# bldc_driver.net
KiCad netlist of a schematic drawn in EAGLE
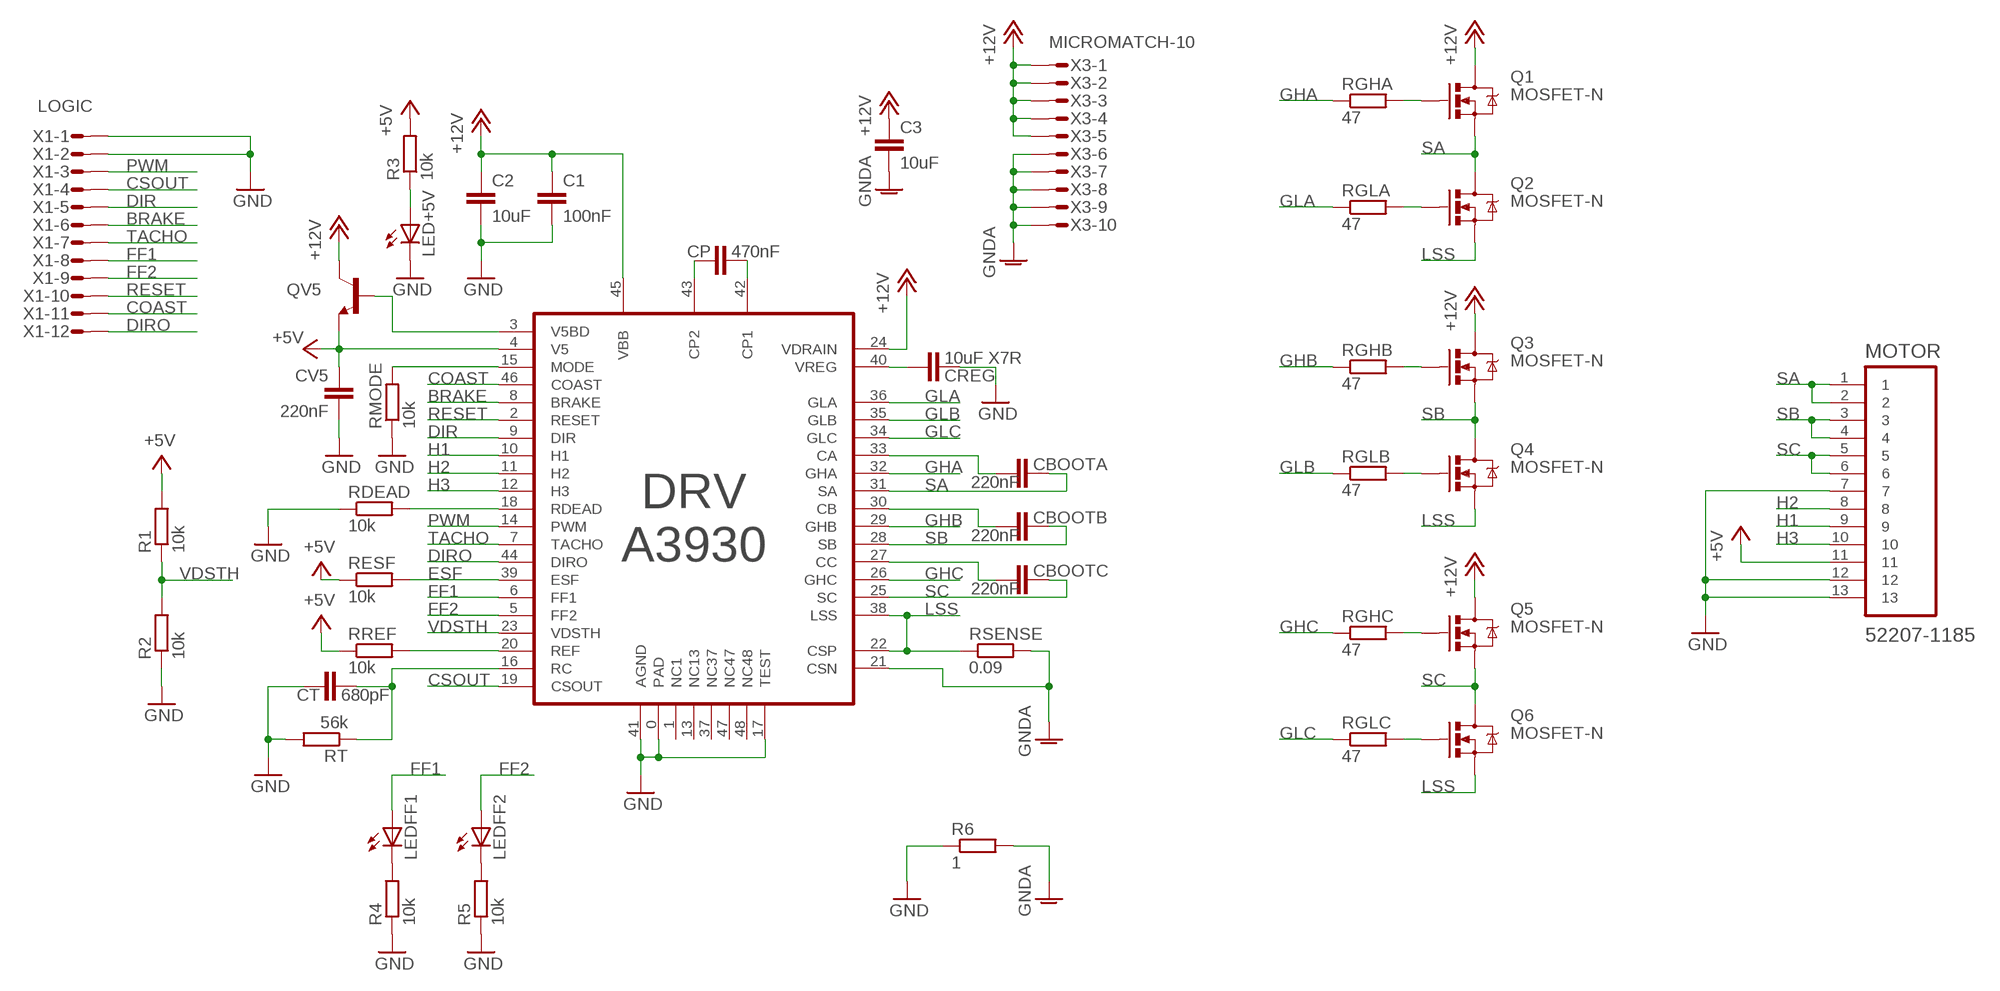
[diagram p0: schematic, sheet 1]

(export (version "E")
  (design (tool "Eeschema 10.0.6"))
  (components
    (comp (ref "C1")
      (value "100nF")
      (footprint "eagle-import:C0603")
      (libsource (lib "eagle-import") (part "C-EUC0603"))
    )
    (comp (ref "C2")
      (value "10uF")
      (footprint "eagle-import:C1206K")
      (libsource (lib "eagle-import") (part "C-EUC1206K"))
    )
    (comp (ref "C3")
      (value "10uF")
      (footprint "eagle-import:C1206K")
      (libsource (lib "eagle-import") (part "C-EUC1206K"))
    )
    (comp (ref "CBOOTA")
      (value "220nF")
      (footprint "eagle-import:C0603")
      (libsource (lib "eagle-import") (part "C-EUC0603"))
    )
    (comp (ref "CBOOTB")
      (value "220nF")
      (footprint "eagle-import:C0603")
      (libsource (lib "eagle-import") (part "C-EUC0603"))
    )
    (comp (ref "CBOOTC")
      (value "220nF")
      (footprint "eagle-import:C0603")
      (libsource (lib "eagle-import") (part "C-EUC0603"))
    )
    (comp (ref "CP")
      (value "470nF")
      (footprint "eagle-import:C0603")
      (libsource (lib "eagle-import") (part "C-EUC0603"))
    )
    (comp (ref "CREG")
      (value "10uF X7R")
      (footprint "eagle-import:C1206K")
      (libsource (lib "eagle-import") (part "C-EUC1206K"))
    )
    (comp (ref "CT")
      (value "680pF")
      (footprint "eagle-import:C0603")
      (libsource (lib "eagle-import") (part "C-EUC0603"))
    )
    (comp (ref "CV5")
      (value "220nF")
      (footprint "eagle-import:C0603")
      (libsource (lib "eagle-import") (part "C-EUC0603"))
    )
    (comp (ref "DRV")
      (value "A3930")
      (footprint "eagle-import:LQFP-48")
      (libsource (lib "eagle-import") (part "A3930"))
    )
    (comp (ref "LED+5V")
      (value "LEDCHIPLED_0603")
      (footprint "eagle-import:CHIPLED_0603")
      (libsource (lib "eagle-import") (part "LEDCHIPLED_0603"))
    )
    (comp (ref "LEDFF1")
      (value "LEDCHIPLED_0603")
      (footprint "eagle-import:CHIPLED_0603")
      (libsource (lib "eagle-import") (part "LEDCHIPLED_0603"))
    )
    (comp (ref "LEDFF2")
      (value "LEDCHIPLED_0603")
      (footprint "eagle-import:CHIPLED_0603")
      (libsource (lib "eagle-import") (part "LEDCHIPLED_0603"))
    )
    (comp (ref "MOTOR")
      (value "52207-1185")
      (footprint "eagle-import:MOLEX_52207-1185")
      (fields (field (name "MPN") "52207-1085"))
      (libsource (lib "eagle-import") (part "52207-1185"))
    )
    (comp (ref "Q1")
      (value "MOSFET-N")
      (footprint "eagle-import:SO08")
      (libsource (lib "eagle-import") (part "MOSFET-NCHANNELFDS6630A"))
    )
    (comp (ref "Q2")
      (value "MOSFET-N")
      (footprint "eagle-import:SO08")
      (libsource (lib "eagle-import") (part "MOSFET-NCHANNELFDS6630A"))
    )
    (comp (ref "Q3")
      (value "MOSFET-N")
      (footprint "eagle-import:SO08")
      (libsource (lib "eagle-import") (part "MOSFET-NCHANNELFDS6630A"))
    )
    (comp (ref "Q4")
      (value "MOSFET-N")
      (footprint "eagle-import:SO08")
      (libsource (lib "eagle-import") (part "MOSFET-NCHANNELFDS6630A"))
    )
    (comp (ref "Q5")
      (value "MOSFET-N")
      (footprint "eagle-import:SO08")
      (libsource (lib "eagle-import") (part "MOSFET-NCHANNELFDS6630A"))
    )
    (comp (ref "Q6")
      (value "MOSFET-N")
      (footprint "eagle-import:SO08")
      (libsource (lib "eagle-import") (part "MOSFET-NCHANNELFDS6630A"))
    )
    (comp (ref "QV5")
      (value "TRANSISTOR_NPNSOT23")
      (footprint "eagle-import:SOT23")
      (libsource (lib "eagle-import") (part "TRANSISTOR_NPNSOT23"))
    )
    (comp (ref "R1")
      (value "10k")
      (footprint "eagle-import:R0603")
      (libsource (lib "eagle-import") (part "R-EU_R0603"))
    )
    (comp (ref "R2")
      (value "10k")
      (footprint "eagle-import:R0603")
      (libsource (lib "eagle-import") (part "R-EU_R0603"))
    )
    (comp (ref "R3")
      (value "10k")
      (footprint "eagle-import:R0603")
      (libsource (lib "eagle-import") (part "R-EU_R0603"))
    )
    (comp (ref "R4")
      (value "10k")
      (footprint "eagle-import:R0603")
      (libsource (lib "eagle-import") (part "R-EU_R0603"))
    )
    (comp (ref "R5")
      (value "10k")
      (footprint "eagle-import:R0603")
      (libsource (lib "eagle-import") (part "R-EU_R0603"))
    )
    (comp (ref "R6")
      (value "1")
      (footprint "eagle-import:R0603")
      (libsource (lib "eagle-import") (part "R-EU_R0603"))
    )
    (comp (ref "RDEAD")
      (value "10k")
      (footprint "eagle-import:R0603")
      (libsource (lib "eagle-import") (part "R-EU_R0603"))
    )
    (comp (ref "RESF")
      (value "10k")
      (footprint "eagle-import:R0603")
      (libsource (lib "eagle-import") (part "R-EU_R0603"))
    )
    (comp (ref "RGHA")
      (value "47")
      (footprint "eagle-import:R0603")
      (libsource (lib "eagle-import") (part "R-EU_R0603"))
    )
    (comp (ref "RGHB")
      (value "47")
      (footprint "eagle-import:R0603")
      (libsource (lib "eagle-import") (part "R-EU_R0603"))
    )
    (comp (ref "RGHC")
      (value "47")
      (footprint "eagle-import:R0603")
      (libsource (lib "eagle-import") (part "R-EU_R0603"))
    )
    (comp (ref "RGLA")
      (value "47")
      (footprint "eagle-import:R0603")
      (libsource (lib "eagle-import") (part "R-EU_R0603"))
    )
    (comp (ref "RGLB")
      (value "47")
      (footprint "eagle-import:R0603")
      (libsource (lib "eagle-import") (part "R-EU_R0603"))
    )
    (comp (ref "RGLC")
      (value "47")
      (footprint "eagle-import:R0603")
      (libsource (lib "eagle-import") (part "R-EU_R0603"))
    )
    (comp (ref "RMODE")
      (value "10k")
      (footprint "eagle-import:R0603")
      (libsource (lib "eagle-import") (part "R-EU_R0603"))
    )
    (comp (ref "RREF")
      (value "10k")
      (footprint "eagle-import:R0603")
      (libsource (lib "eagle-import") (part "R-EU_R0603"))
    )
    (comp (ref "RSENSE")
      (value "0.09")
      (footprint "eagle-import:R2010")
      (libsource (lib "eagle-import") (part "R-EU_R2010"))
    )
    (comp (ref "RT")
      (value "56k")
      (footprint "eagle-import:R0603")
      (libsource (lib "eagle-import") (part "R-EU_R0603"))
    )
    (comp (ref "X1")
      (value "LOGIC")
      (footprint "eagle-import:MICROMATCH-12")
      (fields (field (name "MF") "FARNELL") (field (name "MPN") "8-215464-2"))
      (libsource (lib "eagle-import") (part "MICROMATCH-12"))
    )
    (comp (ref "X3")
      (value "MICROMATCH-10")
      (footprint "eagle-import:MICROMATCH-10")
      (fields (field (name "MF") "FARNELL") (field (name "MPN") "8-215464-0"))
      (libsource (lib "eagle-import") (part "MICROMATCH-10"))
    )
  )
  (nets
    (net (code "1") (name "+5V") (class "Default")
      (node (ref "CV5") (pin "2") (pinfunction "2_2") (pintype "passive"))
      (node (ref "DRV") (pin "4") (pinfunction "V5_4") (pintype "bidirectional"))
      (node (ref "MOTOR") (pin "11") (pinfunction "11_11") (pintype "passive"))
      (node (ref "QV5") (pin "2") (pinfunction "E_2") (pintype "passive"))
      (node (ref "R1") (pin "2") (pinfunction "2_2") (pintype "passive"))
      (node (ref "R3") (pin "2") (pinfunction "2_2") (pintype "passive"))
      (node (ref "RESF") (pin "1") (pinfunction "1_1") (pintype "passive"))
      (node (ref "RREF") (pin "1") (pinfunction "1_1") (pintype "passive"))
    )
    (net (code "2") (name "+12V") (class "Default")
      (node (ref "C1") (pin "1") (pinfunction "1_1") (pintype "passive"))
      (node (ref "C2") (pin "1") (pinfunction "1_1") (pintype "passive"))
      (node (ref "C3") (pin "1") (pinfunction "1_1") (pintype "passive"))
      (node (ref "DRV") (pin "24") (pinfunction "VDRAIN_24") (pintype "bidirectional"))
      (node (ref "DRV") (pin "45") (pinfunction "VBB_45") (pintype "bidirectional"))
      (node (ref "Q1") (pin "5") (pinfunction "D_5") (pintype "passive"))
      (node (ref "Q1") (pin "6") (pinfunction "D_6") (pintype "passive"))
      (node (ref "Q1") (pin "7") (pinfunction "D_7") (pintype "passive"))
      (node (ref "Q1") (pin "8") (pinfunction "D_8") (pintype "passive"))
      (node (ref "Q3") (pin "5") (pinfunction "D_5") (pintype "passive"))
      (node (ref "Q3") (pin "6") (pinfunction "D_6") (pintype "passive"))
      (node (ref "Q3") (pin "7") (pinfunction "D_7") (pintype "passive"))
      (node (ref "Q3") (pin "8") (pinfunction "D_8") (pintype "passive"))
      (node (ref "Q5") (pin "5") (pinfunction "D_5") (pintype "passive"))
      (node (ref "Q5") (pin "6") (pinfunction "D_6") (pintype "passive"))
      (node (ref "Q5") (pin "7") (pinfunction "D_7") (pintype "passive"))
      (node (ref "Q5") (pin "8") (pinfunction "D_8") (pintype "passive"))
      (node (ref "QV5") (pin "3") (pinfunction "C_3") (pintype "passive"))
      (node (ref "X3") (pin "1") (pinfunction "S_1") (pintype "passive"))
      (node (ref "X3") (pin "2") (pinfunction "S_2") (pintype "passive"))
      (node (ref "X3") (pin "3") (pinfunction "S_3") (pintype "passive"))
      (node (ref "X3") (pin "4") (pinfunction "S_4") (pintype "passive"))
      (node (ref "X3") (pin "5") (pinfunction "S_5") (pintype "passive"))
    )
    (net (code "3") (name "/BRAKE") (class "Default")
      (node (ref "DRV") (pin "8") (pinfunction "BRAKE_8") (pintype "bidirectional"))
      (node (ref "X1") (pin "6") (pinfunction "S_6") (pintype "passive"))
    )
    (net (code "4") (name "/COAST") (class "Default")
      (node (ref "DRV") (pin "46") (pinfunction "COAST_46") (pintype "bidirectional"))
      (node (ref "X1") (pin "11") (pinfunction "S_11") (pintype "passive"))
    )
    (net (code "5") (name "/CSOUT") (class "Default")
      (node (ref "DRV") (pin "19") (pinfunction "CSOUT_19") (pintype "bidirectional"))
      (node (ref "X1") (pin "4") (pinfunction "S_4") (pintype "passive"))
    )
    (net (code "6") (name "/DIR") (class "Default")
      (node (ref "DRV") (pin "9") (pinfunction "DIR_9") (pintype "bidirectional"))
      (node (ref "X1") (pin "5") (pinfunction "S_5") (pintype "passive"))
    )
    (net (code "7") (name "/DIRO") (class "Default")
      (node (ref "DRV") (pin "44") (pinfunction "DIRO_44") (pintype "bidirectional"))
      (node (ref "X1") (pin "12") (pinfunction "S_12") (pintype "passive"))
    )
    (net (code "8") (name "/ESF") (class "Default")
      (node (ref "DRV") (pin "39") (pinfunction "ESF_39") (pintype "bidirectional"))
      (node (ref "RESF") (pin "2") (pinfunction "2_2") (pintype "passive"))
    )
    (net (code "9") (name "/FF1") (class "Default")
      (node (ref "DRV") (pin "6") (pinfunction "FF1_6") (pintype "bidirectional"))
      (node (ref "LEDFF1") (pin "A") (pinfunction "A_A") (pintype "passive"))
      (node (ref "X1") (pin "8") (pinfunction "S_8") (pintype "passive"))
    )
    (net (code "10") (name "/FF2") (class "Default")
      (node (ref "DRV") (pin "5") (pinfunction "FF2_5") (pintype "bidirectional"))
      (node (ref "LEDFF2") (pin "A") (pinfunction "A_A") (pintype "passive"))
      (node (ref "X1") (pin "9") (pinfunction "S_9") (pintype "passive"))
    )
    (net (code "11") (name "/GHA") (class "Default")
      (node (ref "DRV") (pin "32") (pinfunction "GHA_32") (pintype "bidirectional"))
      (node (ref "RGHA") (pin "1") (pinfunction "1_1") (pintype "passive"))
    )
    (net (code "12") (name "/GHB") (class "Default")
      (node (ref "DRV") (pin "29") (pinfunction "GHB_29") (pintype "bidirectional"))
      (node (ref "RGHB") (pin "1") (pinfunction "1_1") (pintype "passive"))
    )
    (net (code "13") (name "/GHC") (class "Default")
      (node (ref "DRV") (pin "26") (pinfunction "GHC_26") (pintype "bidirectional"))
      (node (ref "RGHC") (pin "1") (pinfunction "1_1") (pintype "passive"))
    )
    (net (code "14") (name "/GLA") (class "Default")
      (node (ref "DRV") (pin "36") (pinfunction "GLA_36") (pintype "bidirectional"))
      (node (ref "RGLA") (pin "1") (pinfunction "1_1") (pintype "passive"))
    )
    (net (code "15") (name "/GLB") (class "Default")
      (node (ref "DRV") (pin "35") (pinfunction "GLB_35") (pintype "bidirectional"))
      (node (ref "RGLB") (pin "1") (pinfunction "1_1") (pintype "passive"))
    )
    (net (code "16") (name "/GLC") (class "Default")
      (node (ref "DRV") (pin "34") (pinfunction "GLC_34") (pintype "bidirectional"))
      (node (ref "RGLC") (pin "1") (pinfunction "1_1") (pintype "passive"))
    )
    (net (code "17") (name "/H1") (class "Default")
      (node (ref "DRV") (pin "10") (pinfunction "H1_10") (pintype "bidirectional"))
      (node (ref "MOTOR") (pin "9") (pinfunction "9_9") (pintype "passive"))
    )
    (net (code "18") (name "/H2") (class "Default")
      (node (ref "DRV") (pin "11") (pinfunction "H2_11") (pintype "bidirectional"))
      (node (ref "MOTOR") (pin "8") (pinfunction "8_8") (pintype "passive"))
    )
    (net (code "19") (name "/H3") (class "Default")
      (node (ref "DRV") (pin "12") (pinfunction "H3_12") (pintype "bidirectional"))
      (node (ref "MOTOR") (pin "10") (pinfunction "10_10") (pintype "passive"))
    )
    (net (code "20") (name "/LSS") (class "Default")
      (node (ref "DRV") (pin "22") (pinfunction "CSP_22") (pintype "bidirectional"))
      (node (ref "DRV") (pin "38") (pinfunction "LSS_38") (pintype "bidirectional"))
      (node (ref "Q2") (pin "1") (pinfunction "S_1") (pintype "passive"))
      (node (ref "Q2") (pin "2") (pinfunction "S_2") (pintype "passive"))
      (node (ref "Q2") (pin "3") (pinfunction "S_3") (pintype "passive"))
      (node (ref "Q4") (pin "1") (pinfunction "S_1") (pintype "passive"))
      (node (ref "Q4") (pin "2") (pinfunction "S_2") (pintype "passive"))
      (node (ref "Q4") (pin "3") (pinfunction "S_3") (pintype "passive"))
      (node (ref "Q6") (pin "1") (pinfunction "S_1") (pintype "passive"))
      (node (ref "Q6") (pin "2") (pinfunction "S_2") (pintype "passive"))
      (node (ref "Q6") (pin "3") (pinfunction "S_3") (pintype "passive"))
      (node (ref "RSENSE") (pin "1") (pinfunction "1_1") (pintype "passive"))
    )
    (net (code "21") (name "/PWM") (class "Default")
      (node (ref "DRV") (pin "14") (pinfunction "PWM_14") (pintype "bidirectional"))
      (node (ref "X1") (pin "3") (pinfunction "S_3") (pintype "passive"))
    )
    (net (code "22") (name "/RESET") (class "Default")
      (node (ref "DRV") (pin "2") (pinfunction "RESET_2") (pintype "bidirectional"))
      (node (ref "X1") (pin "10") (pinfunction "S_10") (pintype "passive"))
    )
    (net (code "23") (name "/SA") (class "Default")
      (node (ref "CBOOTA") (pin "2") (pinfunction "2_2") (pintype "passive"))
      (node (ref "DRV") (pin "31") (pinfunction "SA_31") (pintype "bidirectional"))
      (node (ref "MOTOR") (pin "1") (pinfunction "1_1") (pintype "passive"))
      (node (ref "MOTOR") (pin "2") (pinfunction "2_2") (pintype "passive"))
      (node (ref "Q1") (pin "1") (pinfunction "S_1") (pintype "passive"))
      (node (ref "Q1") (pin "2") (pinfunction "S_2") (pintype "passive"))
      (node (ref "Q1") (pin "3") (pinfunction "S_3") (pintype "passive"))
      (node (ref "Q2") (pin "5") (pinfunction "D_5") (pintype "passive"))
      (node (ref "Q2") (pin "6") (pinfunction "D_6") (pintype "passive"))
      (node (ref "Q2") (pin "7") (pinfunction "D_7") (pintype "passive"))
      (node (ref "Q2") (pin "8") (pinfunction "D_8") (pintype "passive"))
    )
    (net (code "24") (name "/SB") (class "Default")
      (node (ref "CBOOTB") (pin "2") (pinfunction "2_2") (pintype "passive"))
      (node (ref "DRV") (pin "28") (pinfunction "SB_28") (pintype "bidirectional"))
      (node (ref "MOTOR") (pin "3") (pinfunction "3_3") (pintype "passive"))
      (node (ref "MOTOR") (pin "4") (pinfunction "4_4") (pintype "passive"))
      (node (ref "Q3") (pin "1") (pinfunction "S_1") (pintype "passive"))
      (node (ref "Q3") (pin "2") (pinfunction "S_2") (pintype "passive"))
      (node (ref "Q3") (pin "3") (pinfunction "S_3") (pintype "passive"))
      (node (ref "Q4") (pin "5") (pinfunction "D_5") (pintype "passive"))
      (node (ref "Q4") (pin "6") (pinfunction "D_6") (pintype "passive"))
      (node (ref "Q4") (pin "7") (pinfunction "D_7") (pintype "passive"))
      (node (ref "Q4") (pin "8") (pinfunction "D_8") (pintype "passive"))
    )
    (net (code "25") (name "/SC") (class "Default")
      (node (ref "CBOOTC") (pin "2") (pinfunction "2_2") (pintype "passive"))
      (node (ref "DRV") (pin "25") (pinfunction "SC_25") (pintype "bidirectional"))
      (node (ref "MOTOR") (pin "5") (pinfunction "5_5") (pintype "passive"))
      (node (ref "MOTOR") (pin "6") (pinfunction "6_6") (pintype "passive"))
      (node (ref "Q5") (pin "1") (pinfunction "S_1") (pintype "passive"))
      (node (ref "Q5") (pin "2") (pinfunction "S_2") (pintype "passive"))
      (node (ref "Q5") (pin "3") (pinfunction "S_3") (pintype "passive"))
      (node (ref "Q6") (pin "5") (pinfunction "D_5") (pintype "passive"))
      (node (ref "Q6") (pin "6") (pinfunction "D_6") (pintype "passive"))
      (node (ref "Q6") (pin "7") (pinfunction "D_7") (pintype "passive"))
      (node (ref "Q6") (pin "8") (pinfunction "D_8") (pintype "passive"))
    )
    (net (code "26") (name "/TACHO") (class "Default")
      (node (ref "DRV") (pin "7") (pinfunction "TACHO_7") (pintype "bidirectional"))
      (node (ref "X1") (pin "7") (pinfunction "S_7") (pintype "passive"))
    )
    (net (code "27") (name "/VDSTH") (class "Default")
      (node (ref "DRV") (pin "23") (pinfunction "VDSTH_23") (pintype "bidirectional"))
      (node (ref "R1") (pin "1") (pinfunction "1_1") (pintype "passive"))
      (node (ref "R2") (pin "2") (pinfunction "2_2") (pintype "passive"))
    )
    (net (code "28") (name "GND") (class "Default")
      (node (ref "C1") (pin "2") (pinfunction "2_2") (pintype "passive"))
      (node (ref "C2") (pin "2") (pinfunction "2_2") (pintype "passive"))
      (node (ref "CREG") (pin "2") (pinfunction "2_2") (pintype "passive"))
      (node (ref "CT") (pin "2") (pinfunction "2_2") (pintype "passive"))
      (node (ref "CV5") (pin "1") (pinfunction "1_1") (pintype "passive"))
      (node (ref "DRV") (pin "0") (pinfunction "PAD_0") (pintype "bidirectional"))
      (node (ref "DRV") (pin "17") (pinfunction "TEST_17") (pintype "bidirectional"))
      (node (ref "DRV") (pin "41") (pinfunction "AGND_41") (pintype "bidirectional"))
      (node (ref "LED+5V") (pin "C") (pinfunction "C_C") (pintype "passive"))
      (node (ref "MOTOR") (pin "12") (pinfunction "12_12") (pintype "passive"))
      (node (ref "MOTOR") (pin "13") (pinfunction "13_13") (pintype "passive"))
      (node (ref "MOTOR") (pin "7") (pinfunction "7_7") (pintype "passive"))
      (node (ref "R2") (pin "1") (pinfunction "1_1") (pintype "passive"))
      (node (ref "R4") (pin "1") (pinfunction "1_1") (pintype "passive"))
      (node (ref "R5") (pin "1") (pinfunction "1_1") (pintype "passive"))
      (node (ref "R6") (pin "1") (pinfunction "1_1") (pintype "passive"))
      (node (ref "RDEAD") (pin "1") (pinfunction "1_1") (pintype "passive"))
      (node (ref "RMODE") (pin "1") (pinfunction "1_1") (pintype "passive"))
      (node (ref "RT") (pin "2") (pinfunction "2_2") (pintype "passive"))
      (node (ref "X1") (pin "1") (pinfunction "S_1") (pintype "passive"))
      (node (ref "X1") (pin "2") (pinfunction "S_2") (pintype "passive"))
    )
    (net (code "29") (name "GNDA") (class "Default")
      (node (ref "C3") (pin "2") (pinfunction "2_2") (pintype "passive"))
      (node (ref "DRV") (pin "21") (pinfunction "CSN_21") (pintype "bidirectional"))
      (node (ref "R6") (pin "2") (pinfunction "2_2") (pintype "passive"))
      (node (ref "RSENSE") (pin "2") (pinfunction "2_2") (pintype "passive"))
      (node (ref "X3") (pin "10") (pinfunction "S_10") (pintype "passive"))
      (node (ref "X3") (pin "6") (pinfunction "S_6") (pintype "passive"))
      (node (ref "X3") (pin "7") (pinfunction "S_7") (pintype "passive"))
      (node (ref "X3") (pin "8") (pinfunction "S_8") (pintype "passive"))
      (node (ref "X3") (pin "9") (pinfunction "S_9") (pintype "passive"))
    )
    (net (code "30") (name "Net-(DRV-CA)") (class "Default")
      (node (ref "CBOOTA") (pin "1") (pinfunction "1_1") (pintype "passive"))
      (node (ref "DRV") (pin "33") (pinfunction "CA_33") (pintype "bidirectional"))
    )
    (net (code "31") (name "Net-(DRV-CB)") (class "Default")
      (node (ref "CBOOTB") (pin "1") (pinfunction "1_1") (pintype "passive"))
      (node (ref "DRV") (pin "30") (pinfunction "CB_30") (pintype "bidirectional"))
    )
    (net (code "32") (name "Net-(DRV-CC)") (class "Default")
      (node (ref "CBOOTC") (pin "1") (pinfunction "1_1") (pintype "passive"))
      (node (ref "DRV") (pin "27") (pinfunction "CC_27") (pintype "bidirectional"))
    )
    (net (code "33") (name "Net-(DRV-CP1)") (class "Default")
      (node (ref "CP") (pin "1") (pinfunction "1_1") (pintype "passive"))
      (node (ref "DRV") (pin "42") (pinfunction "CP1_42") (pintype "bidirectional"))
    )
    (net (code "34") (name "Net-(DRV-CP2)") (class "Default")
      (node (ref "CP") (pin "2") (pinfunction "2_2") (pintype "passive"))
      (node (ref "DRV") (pin "43") (pinfunction "CP2_43") (pintype "bidirectional"))
    )
    (net (code "35") (name "Net-(DRV-MODE)") (class "Default")
      (node (ref "DRV") (pin "15") (pinfunction "MODE_15") (pintype "bidirectional"))
      (node (ref "RMODE") (pin "2") (pinfunction "2_2") (pintype "passive"))
    )
    (net (code "36") (name "Net-(DRV-RC)") (class "Default")
      (node (ref "CT") (pin "1") (pinfunction "1_1") (pintype "passive"))
      (node (ref "DRV") (pin "16") (pinfunction "RC_16") (pintype "bidirectional"))
      (node (ref "RT") (pin "1") (pinfunction "1_1") (pintype "passive"))
    )
    (net (code "37") (name "Net-(DRV-RDEAD)") (class "Default")
      (node (ref "DRV") (pin "18") (pinfunction "RDEAD_18") (pintype "bidirectional"))
      (node (ref "RDEAD") (pin "2") (pinfunction "2_2") (pintype "passive"))
    )
    (net (code "38") (name "Net-(DRV-REF)") (class "Default")
      (node (ref "DRV") (pin "20") (pinfunction "REF_20") (pintype "bidirectional"))
      (node (ref "RREF") (pin "2") (pinfunction "2_2") (pintype "passive"))
    )
    (net (code "39") (name "Net-(DRV-V5BD)") (class "Default")
      (node (ref "DRV") (pin "3") (pinfunction "V5BD_3") (pintype "bidirectional"))
      (node (ref "QV5") (pin "1") (pinfunction "B_1") (pintype "passive"))
    )
    (net (code "40") (name "Net-(DRV-VREG)") (class "Default")
      (node (ref "CREG") (pin "1") (pinfunction "1_1") (pintype "passive"))
      (node (ref "DRV") (pin "40") (pinfunction "VREG_40") (pintype "bidirectional"))
    )
    (net (code "41") (name "Net-(LED+5V-PadA)") (class "Default")
      (node (ref "LED+5V") (pin "A") (pinfunction "A_A") (pintype "passive"))
      (node (ref "R3") (pin "1") (pinfunction "1_1") (pintype "passive"))
    )
    (net (code "42") (name "Net-(LEDFF1-PadC)") (class "Default")
      (node (ref "LEDFF1") (pin "C") (pinfunction "C_C") (pintype "passive"))
      (node (ref "R4") (pin "2") (pinfunction "2_2") (pintype "passive"))
    )
    (net (code "43") (name "Net-(LEDFF2-PadC)") (class "Default")
      (node (ref "LEDFF2") (pin "C") (pinfunction "C_C") (pintype "passive"))
      (node (ref "R5") (pin "2") (pinfunction "2_2") (pintype "passive"))
    )
    (net (code "44") (name "Net-(Q1-G)") (class "Default")
      (node (ref "Q1") (pin "4") (pinfunction "G_4") (pintype "passive"))
      (node (ref "RGHA") (pin "2") (pinfunction "2_2") (pintype "passive"))
    )
    (net (code "45") (name "Net-(Q2-G)") (class "Default")
      (node (ref "Q2") (pin "4") (pinfunction "G_4") (pintype "passive"))
      (node (ref "RGLA") (pin "2") (pinfunction "2_2") (pintype "passive"))
    )
    (net (code "46") (name "Net-(Q3-G)") (class "Default")
      (node (ref "Q3") (pin "4") (pinfunction "G_4") (pintype "passive"))
      (node (ref "RGHB") (pin "2") (pinfunction "2_2") (pintype "passive"))
    )
    (net (code "47") (name "Net-(Q4-G)") (class "Default")
      (node (ref "Q4") (pin "4") (pinfunction "G_4") (pintype "passive"))
      (node (ref "RGLB") (pin "2") (pinfunction "2_2") (pintype "passive"))
    )
    (net (code "48") (name "Net-(Q5-G)") (class "Default")
      (node (ref "Q5") (pin "4") (pinfunction "G_4") (pintype "passive"))
      (node (ref "RGHC") (pin "2") (pinfunction "2_2") (pintype "passive"))
    )
    (net (code "49") (name "Net-(Q6-G)") (class "Default")
      (node (ref "Q6") (pin "4") (pinfunction "G_4") (pintype "passive"))
      (node (ref "RGLC") (pin "2") (pinfunction "2_2") (pintype "passive"))
    )
    (net (code "50") (name "unconnected-(DRV-NC1-Pad1)") (class "Default")
      (node (ref "DRV") (pin "1") (pinfunction "NC1_1") (pintype "no_connect"))
    )
    (net (code "51") (name "unconnected-(DRV-NC13-Pad13)") (class "Default")
      (node (ref "DRV") (pin "13") (pinfunction "NC13_13") (pintype "no_connect"))
    )
    (net (code "52") (name "unconnected-(DRV-NC37-Pad37)") (class "Default")
      (node (ref "DRV") (pin "37") (pinfunction "NC37_37") (pintype "no_connect"))
    )
    (net (code "53") (name "unconnected-(DRV-NC47-Pad47)") (class "Default")
      (node (ref "DRV") (pin "47") (pinfunction "NC47_47") (pintype "no_connect"))
    )
    (net (code "54") (name "unconnected-(DRV-NC48-Pad48)") (class "Default")
      (node (ref "DRV") (pin "48") (pinfunction "NC48_48") (pintype "no_connect"))
    )
  )
)
